# 19_-_USB.net
KiCad netlist of a schematic drawn in Altium Designer
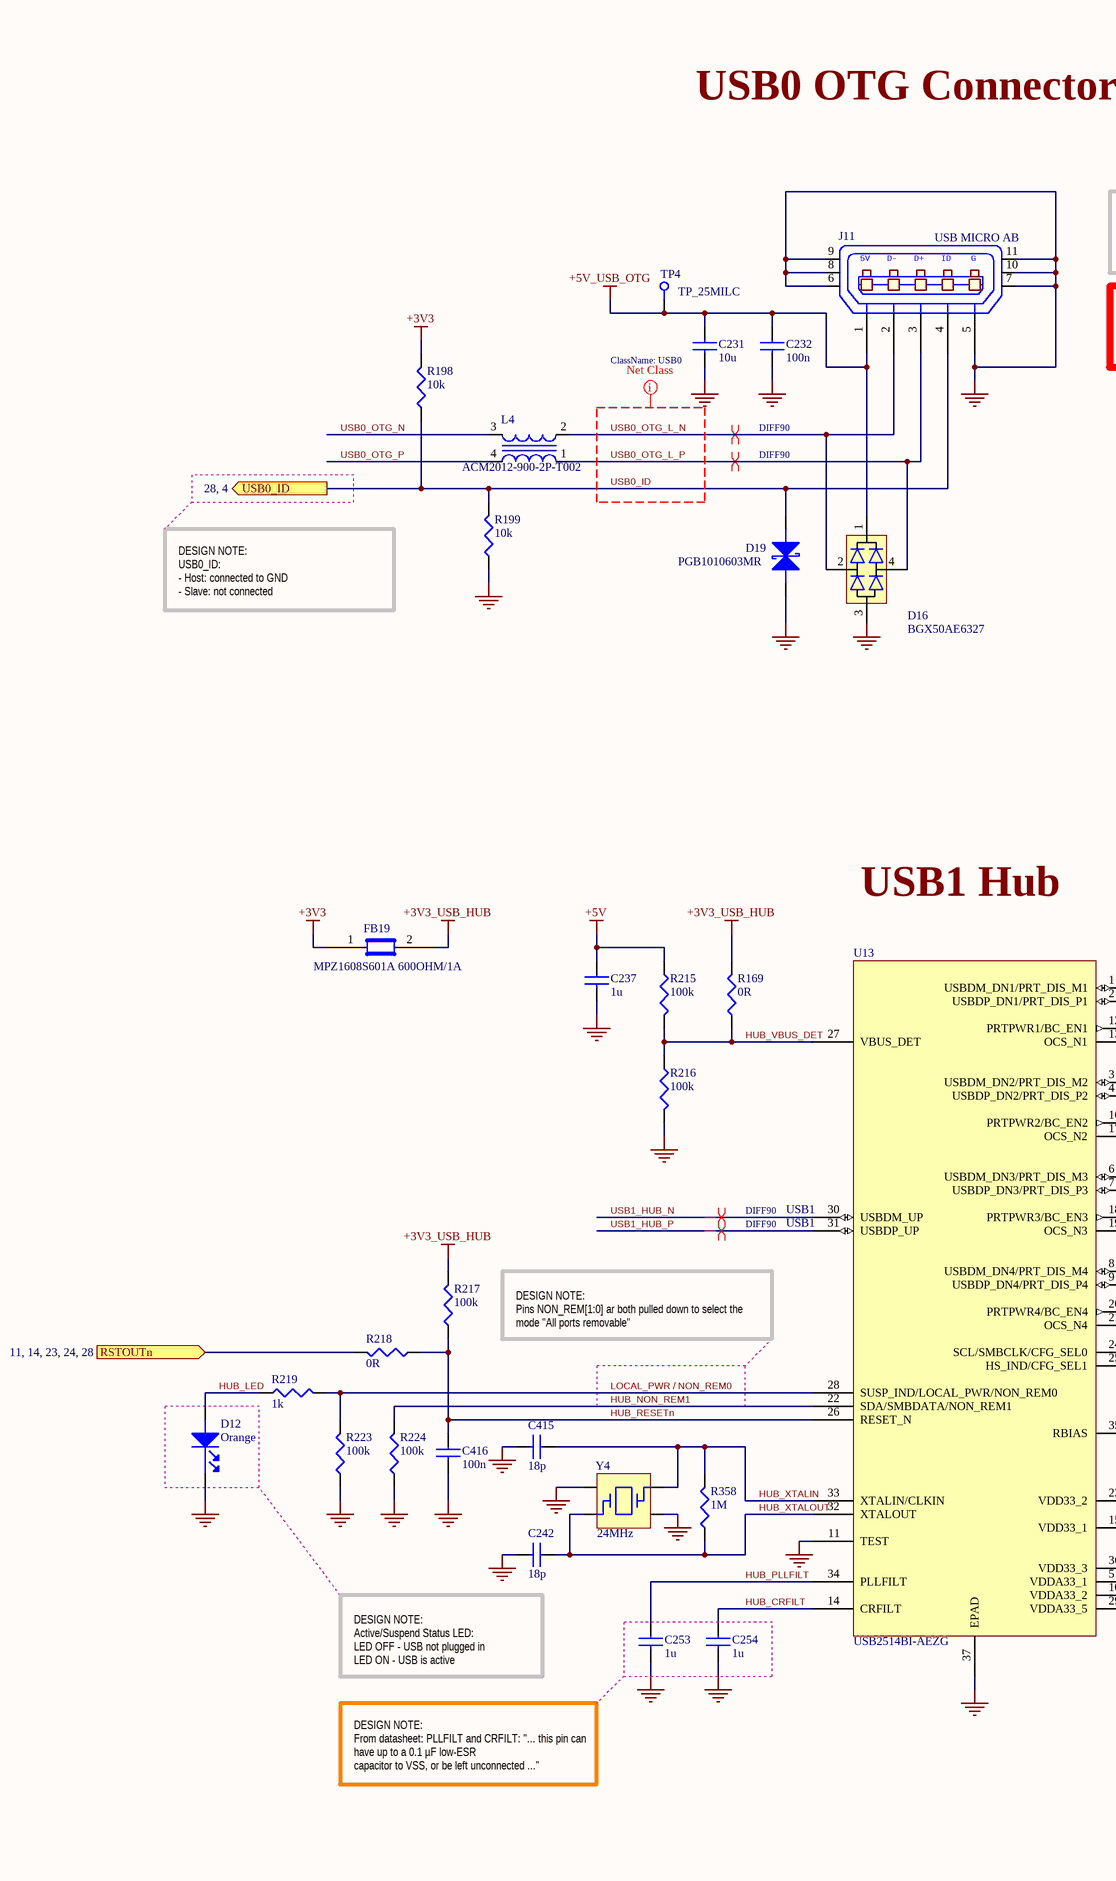
[diagram p0: [19] - USB.SchDoc, left]
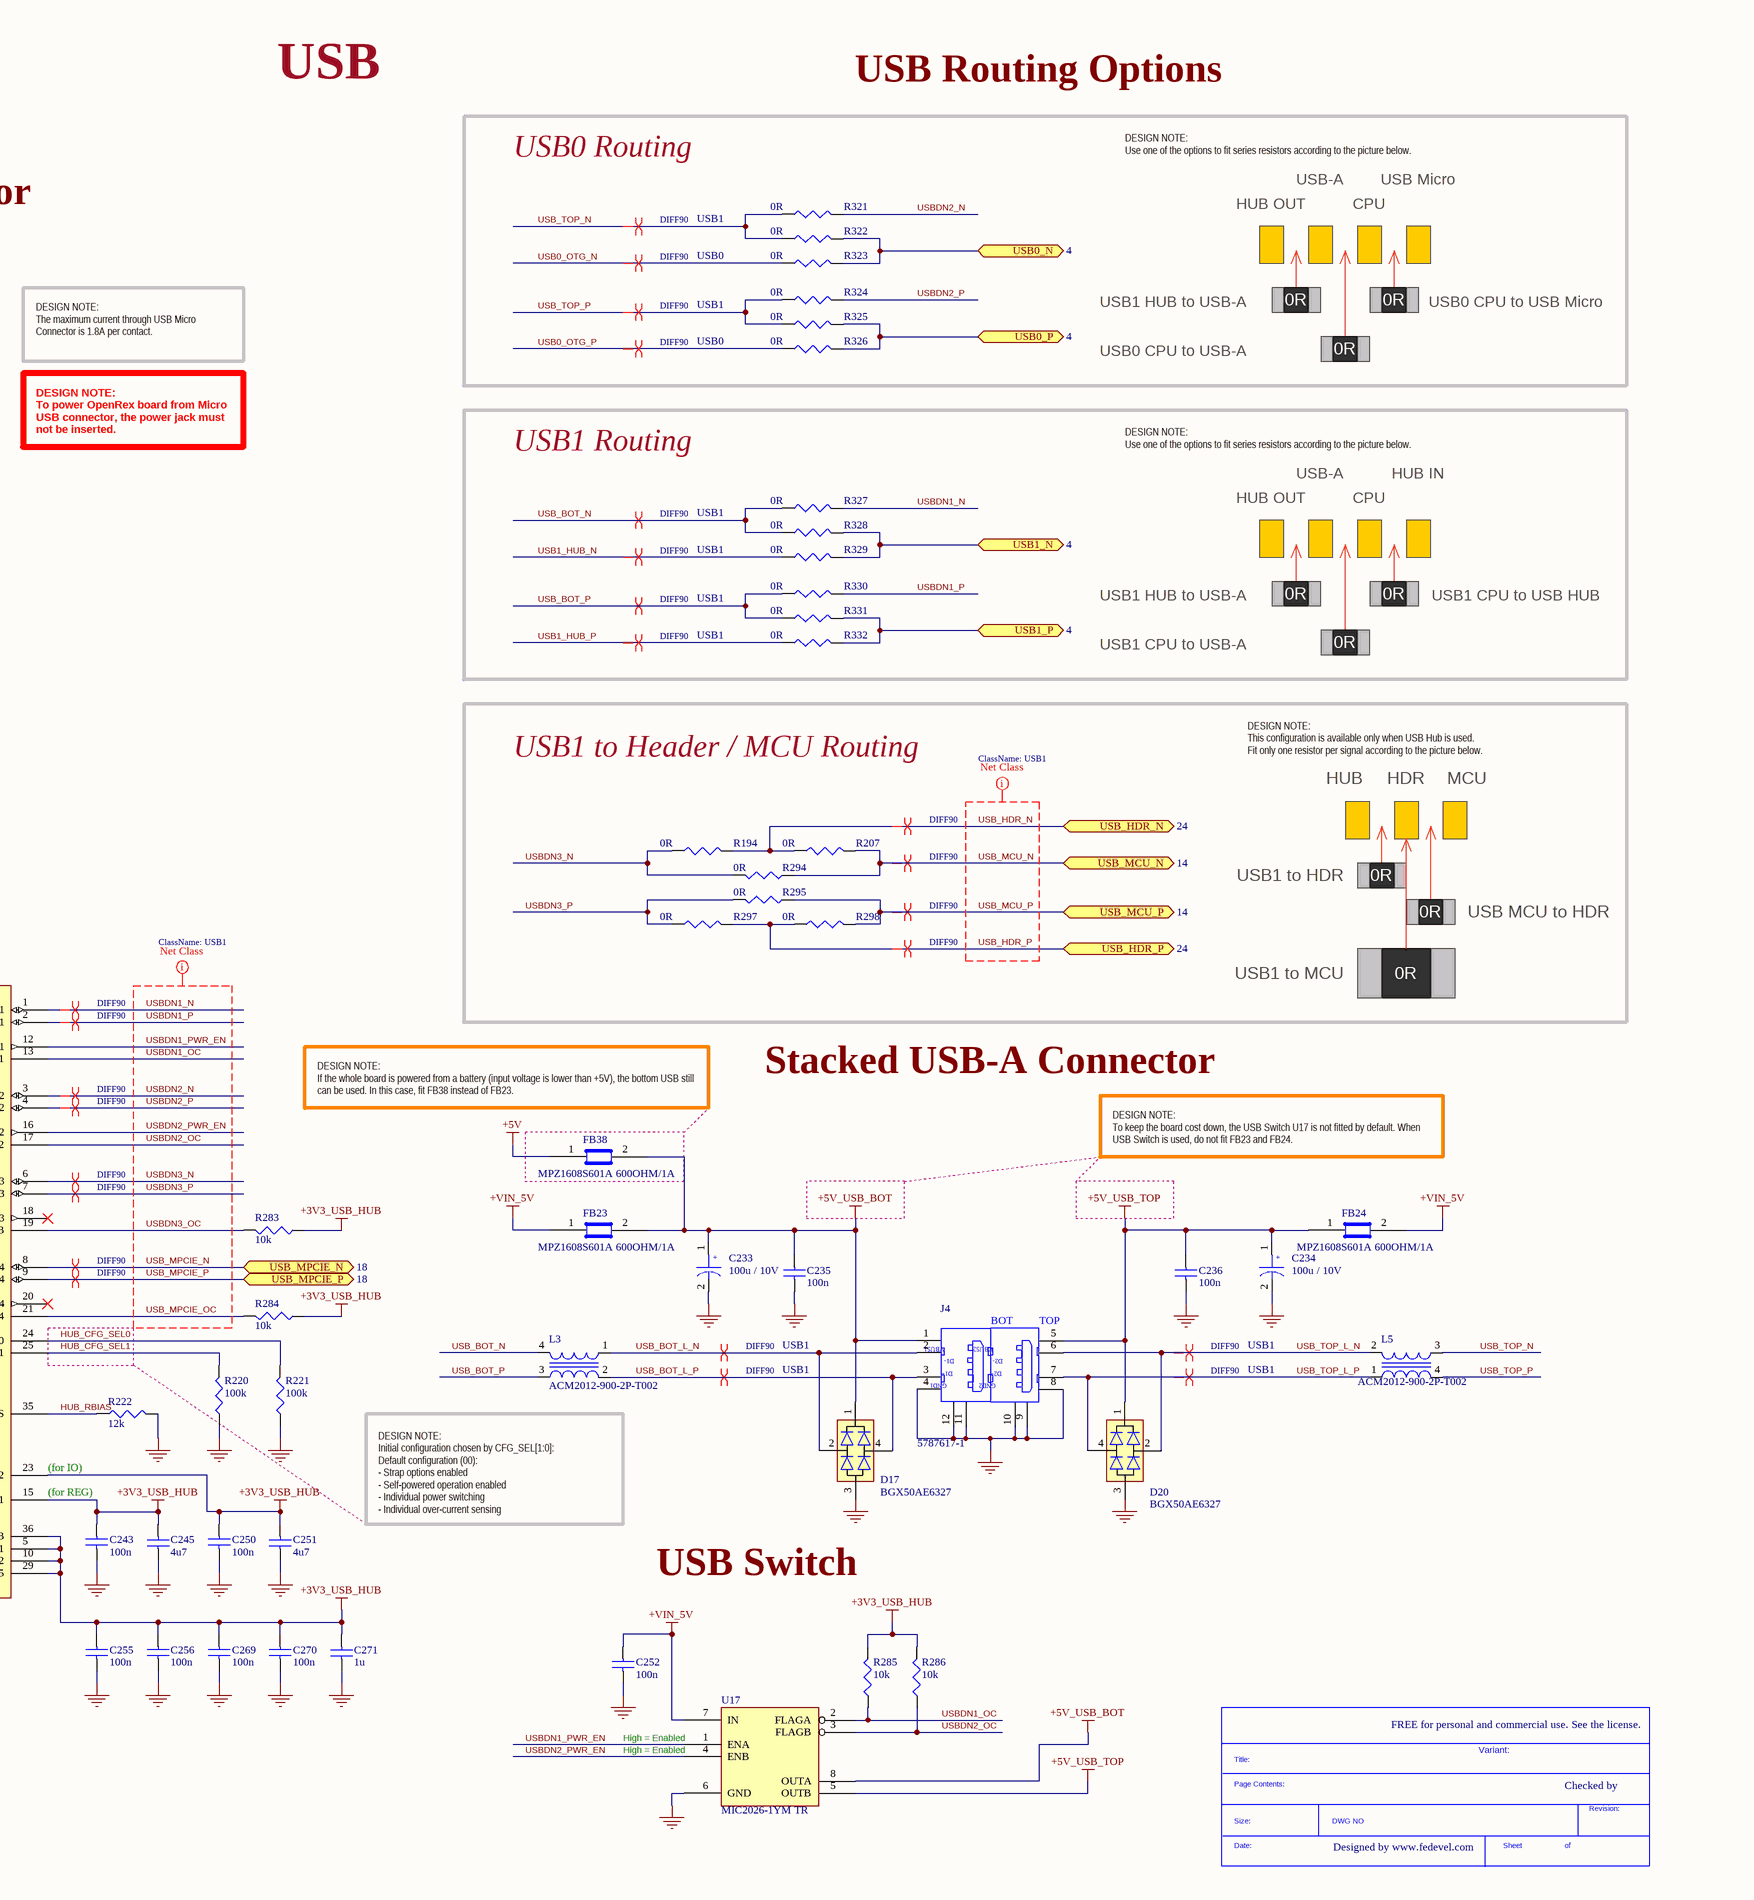
[diagram p1: [19] - USB.SchDoc, right]

(export (version "E")
  (design (tool "Eeschema 10.0.6"))
  (components
    (comp (ref "C231")
      (value "10u")
      (footprint "C0603")
      (description "CAP CER 10UF 6.3V X5R 20% 0603")
      (fields
        (field (name "MANUFACTURER") "TDK Corporation")
        (field (name "MANUFACTURER PART NUMBER") "C1608X5R0J106M")
      )
      (libsource (lib "Integrated_Library_FEDEVEL_APR_2015") (part "C1608X5R0J106M"))
    )
    (comp (ref "C232")
      (value "100n")
      (footprint "C0402")
      (description "CAP CER .10UF 50V X5R 10% 0402")
      (fields
        (field (name "MANUFACTURER") "TDK Corporation")
        (field (name "MANUFACTURER PART NUMBER") "C1005X5R1H104K")
      )
      (libsource (lib "Integrated_Library_FEDEVEL_APR_2015") (part "C1005X5R1H104K"))
    )
    (comp (ref "C233")
      (value "100u / 10V")
      (footprint "C2312")
      (description "CAP TANT 100UF 10V 10% 2312")
      (fields
        (field (name "MANUFACTURER") "AVX Corporation")
        (field (name "MANUFACTURER PART NUMBER") "TPSC107K010R0150")
        (field (name ".CREATOR") "MM")
        (field (name ".CHECKED PCB") "MM")
        (field (name ".CHECKED SCH") "MM")
      )
      (libsource (lib "Integrated_Library_FEDEVEL_APR_2015") (part "TPSC107K010R0150"))
    )
    (comp (ref "C234")
      (value "100u / 10V")
      (footprint "C2312")
      (description "CAP TANT 100UF 10V 10% 2312")
      (fields
        (field (name "MANUFACTURER") "AVX Corporation")
        (field (name "MANUFACTURER PART NUMBER") "TPSC107K010R0150")
        (field (name ".CREATOR") "MM")
        (field (name ".CHECKED PCB") "MM")
        (field (name ".CHECKED SCH") "MM")
      )
      (libsource (lib "Integrated_Library_FEDEVEL_APR_2015") (part "TPSC107K010R0150"))
    )
    (comp (ref "C235")
      (value "100n")
      (footprint "C0402")
      (description "CAP CER .10UF 50V X5R 10% 0402")
      (fields
        (field (name "MANUFACTURER") "TDK Corporation")
        (field (name "MANUFACTURER PART NUMBER") "C1005X5R1H104K")
      )
      (libsource (lib "Integrated_Library_FEDEVEL_APR_2015") (part "C1005X5R1H104K"))
    )
    (comp (ref "C236")
      (value "100n")
      (footprint "C0402")
      (description "CAP CER .10UF 50V X5R 10% 0402")
      (fields
        (field (name "MANUFACTURER") "TDK Corporation")
        (field (name "MANUFACTURER PART NUMBER") "C1005X5R1H104K")
      )
      (libsource (lib "Integrated_Library_FEDEVEL_APR_2015") (part "C1005X5R1H104K"))
    )
    (comp (ref "C237")
      (value "1u")
      (footprint "C0402")
      (description "CAP CER 1.0UF 16V X5R 0402")
      (fields
        (field (name "MANUFACTURER") "TDK Corporation")
        (field (name "MANUFACTURER PART NUMBER") "C1005X5R1C105K")
      )
      (libsource (lib "Integrated_Library_FEDEVEL_APR_2015") (part "C1005X5R1C105K"))
    )
    (comp (ref "C242")
      (value "18p")
      (footprint "C0402")
      (description "CAP CER 18PF 50V C0G 5% 0402")
      (fields
        (field (name "MANUFACTURER") "TDK Corporation")
        (field (name "MANUFACTURER PART NUMBER") "C1005C0G1H180J")
      )
      (libsource (lib "Integrated_Library_FEDEVEL_APR_2015") (part "C1005C0G1H180J"))
    )
    (comp (ref "C243")
      (value "100n")
      (footprint "C0402")
      (description "CAP CER .10UF 50V X5R 10% 0402")
      (fields
        (field (name "MANUFACTURER") "TDK Corporation")
        (field (name "MANUFACTURER PART NUMBER") "C1005X5R1H104K")
      )
      (libsource (lib "Integrated_Library_FEDEVEL_APR_2015") (part "C1005X5R1H104K"))
    )
    (comp (ref "C245")
      (value "4u7")
      (footprint "C0402")
      (description "CAP CER 4.7UF 10V 20% X5R 0402")
      (fields
        (field (name "MANUFACTURER") "TDK Corporation")
        (field (name "MANUFACTURER PART NUMBER") "C1005X5R1A475M")
      )
      (libsource (lib "Integrated_Library_FEDEVEL_APR_2015") (part "C1005X5R1A475M"))
    )
    (comp (ref "C250")
      (value "100n")
      (footprint "C0402")
      (description "CAP CER .10UF 50V X5R 10% 0402")
      (fields
        (field (name "MANUFACTURER") "TDK Corporation")
        (field (name "MANUFACTURER PART NUMBER") "C1005X5R1H104K")
      )
      (libsource (lib "Integrated_Library_FEDEVEL_APR_2015") (part "C1005X5R1H104K"))
    )
    (comp (ref "C251")
      (value "4u7")
      (footprint "C0402")
      (description "CAP CER 4.7UF 10V 20% X5R 0402")
      (fields
        (field (name "MANUFACTURER") "TDK Corporation")
        (field (name "MANUFACTURER PART NUMBER") "C1005X5R1A475M")
      )
      (libsource (lib "Integrated_Library_FEDEVEL_APR_2015") (part "C1005X5R1A475M"))
    )
    (comp (ref "C252")
      (value "100n")
      (footprint "C0402")
      (description "CAP CER .10UF 50V X5R 10% 0402")
      (fields
        (field (name "MANUFACTURER") "TDK Corporation")
        (field (name "MANUFACTURER PART NUMBER") "C1005X5R1H104K")
      )
      (libsource (lib "Integrated_Library_FEDEVEL_APR_2015") (part "C1005X5R1H104K"))
    )
    (comp (ref "C253")
      (value "1u")
      (footprint "C0402")
      (description "CAP CER 1.0UF 16V X5R 0402")
      (fields
        (field (name "MANUFACTURER") "TDK Corporation")
        (field (name "MANUFACTURER PART NUMBER") "C1005X5R1C105K")
      )
      (libsource (lib "Integrated_Library_FEDEVEL_APR_2015") (part "C1005X5R1C105K"))
    )
    (comp (ref "C254")
      (value "1u")
      (footprint "C0402")
      (description "CAP CER 1.0UF 16V X5R 0402")
      (fields
        (field (name "MANUFACTURER") "TDK Corporation")
        (field (name "MANUFACTURER PART NUMBER") "C1005X5R1C105K")
      )
      (libsource (lib "Integrated_Library_FEDEVEL_APR_2015") (part "C1005X5R1C105K"))
    )
    (comp (ref "C255")
      (value "100n")
      (footprint "C0402")
      (description "CAP CER .10UF 50V X5R 10% 0402")
      (fields
        (field (name "MANUFACTURER") "TDK Corporation")
        (field (name "MANUFACTURER PART NUMBER") "C1005X5R1H104K")
      )
      (libsource (lib "Integrated_Library_FEDEVEL_APR_2015") (part "C1005X5R1H104K"))
    )
    (comp (ref "C256")
      (value "100n")
      (footprint "C0402")
      (description "CAP CER .10UF 50V X5R 10% 0402")
      (fields
        (field (name "MANUFACTURER") "TDK Corporation")
        (field (name "MANUFACTURER PART NUMBER") "C1005X5R1H104K")
      )
      (libsource (lib "Integrated_Library_FEDEVEL_APR_2015") (part "C1005X5R1H104K"))
    )
    (comp (ref "C269")
      (value "100n")
      (footprint "C0402")
      (description "CAP CER .10UF 50V X5R 10% 0402")
      (fields
        (field (name "MANUFACTURER") "TDK Corporation")
        (field (name "MANUFACTURER PART NUMBER") "C1005X5R1H104K")
      )
      (libsource (lib "Integrated_Library_FEDEVEL_APR_2015") (part "C1005X5R1H104K"))
    )
    (comp (ref "C270")
      (value "100n")
      (footprint "C0402")
      (description "CAP CER .10UF 50V X5R 10% 0402")
      (fields
        (field (name "MANUFACTURER") "TDK Corporation")
        (field (name "MANUFACTURER PART NUMBER") "C1005X5R1H104K")
      )
      (libsource (lib "Integrated_Library_FEDEVEL_APR_2015") (part "C1005X5R1H104K"))
    )
    (comp (ref "C271")
      (value "1u")
      (footprint "C0402")
      (description "CAP CER 1.0UF 16V X5R 0402")
      (fields
        (field (name "MANUFACTURER") "TDK Corporation")
        (field (name "MANUFACTURER PART NUMBER") "C1005X5R1C105K")
      )
      (libsource (lib "Integrated_Library_FEDEVEL_APR_2015") (part "C1005X5R1C105K"))
    )
    (comp (ref "C415")
      (value "18p")
      (footprint "C0402")
      (description "CAP CER 18PF 50V C0G 5% 0402")
      (fields
        (field (name "MANUFACTURER") "TDK Corporation")
        (field (name "MANUFACTURER PART NUMBER") "C1005C0G1H180J")
      )
      (libsource (lib "Integrated_Library_FEDEVEL_APR_2015") (part "C1005C0G1H180J"))
    )
    (comp (ref "C416")
      (value "100n")
      (footprint "C0402")
      (description "CAP CER .10UF 50V X5R 10% 0402")
      (fields
        (field (name "MANUFACTURER") "TDK Corporation")
        (field (name "MANUFACTURER PART NUMBER") "C1005X5R1H104K")
      )
      (libsource (lib "Integrated_Library_FEDEVEL_APR_2015") (part "C1005X5R1H104K"))
    )
    (comp (ref "D12")
      (value "Orange")
      (footprint "LED_0603")
      (description "LED SMARTLED ORANGE 606NM 0603")
      (fields
        (field (name "MANUFACTURER") "OSRAM Opto Semiconductors Inc")
        (field (name "MANUFACTURER PART NUMBER") "LO L29K-H2K1-24-Z")
      )
      (libsource (lib "Integrated_Library_FEDEVEL_APR_2015") (part "LO L29K-H2K1-24-Z"))
    )
    (comp (ref "D16")
      (value "BGX50AE6327")
      (footprint "SOT143")
      (description "DIODE SWITCHING 50V SOT-143")
      (fields (field (name "MANUFACTURER") "Infineon Technologies"))
      (libsource (lib "Integrated_Library_FEDEVEL_APR_2015") (part "BGX50AE6327"))
    )
    (comp (ref "D17")
      (value "BGX50AE6327")
      (footprint "SOT143")
      (description "DIODE SWITCHING 50V SOT-143")
      (fields (field (name "MANUFACTURER") "Infineon Technologies"))
      (libsource (lib "Integrated_Library_FEDEVEL_APR_2015") (part "BGX50AE6327"))
    )
    (comp (ref "D19")
      (value "PGB1010603MR")
      (footprint "C0603")
      (description "SUPPRESSOR ESD 24VDC 0603 SMD")
      (fields (field (name "MANUFACTURER") "Littelfuse Inc") (field (name ".CREATOR") "MM"))
      (libsource (lib "Integrated_Library_FEDEVEL_APR_2015") (part "PGB1010603MR"))
    )
    (comp (ref "D20")
      (value "BGX50AE6327")
      (footprint "SOT143")
      (description "DIODE SWITCHING 50V SOT-143")
      (fields (field (name "MANUFACTURER") "Infineon Technologies"))
      (libsource (lib "") (part "BGX50AE6327_1"))
    )
    (comp (ref "FB19")
      (value "MPZ1608S601A 600OHM/1A")
      (footprint "C0603")
      (description "FERRITE CHIP BEAD 600 OHM SMD 1A")
      (fields
        (field (name "MANUFACTURER") "TDK Corporation")
        (field (name "MANUFACTURER PART NUMBER") "MPZ1608S601A")
      )
      (libsource (lib "Integrated_Library_FEDEVEL_APR_2015") (part "MPZ1608S601A"))
    )
    (comp (ref "FB23")
      (value "MPZ1608S601A 600OHM/1A")
      (footprint "C0603")
      (description "FERRITE CHIP BEAD 600 OHM SMD 1A")
      (fields
        (field (name "MANUFACTURER") "TDK Corporation")
        (field (name "MANUFACTURER PART NUMBER") "MPZ1608S601A")
      )
      (libsource (lib "Integrated_Library_FEDEVEL_APR_2015") (part "MPZ1608S601A"))
    )
    (comp (ref "FB24")
      (value "MPZ1608S601A 600OHM/1A")
      (footprint "C0603")
      (description "FERRITE CHIP BEAD 600 OHM SMD 1A")
      (fields
        (field (name "MANUFACTURER") "TDK Corporation")
        (field (name "MANUFACTURER PART NUMBER") "MPZ1608S601A")
      )
      (libsource (lib "Integrated_Library_FEDEVEL_APR_2015") (part "MPZ1608S601A"))
    )
    (comp (ref "FB38")
      (value "MPZ1608S601A 600OHM/1A")
      (footprint "C0603")
      (description "FERRITE CHIP BEAD 600 OHM SMD 1A")
      (fields
        (field (name "MANUFACTURER") "TDK Corporation")
        (field (name "MANUFACTURER PART NUMBER") "MPZ1608S601A")
      )
      (libsource (lib "Integrated_Library_FEDEVEL_APR_2015") (part "MPZ1608S601A"))
    )
    (comp (ref "J4")
      (value "5787617-1")
      (footprint "USB-2A")
      (description "CONN RCPT R/A 4OVER4POS GOLD PCB")
      (fields
        (field (name "MANUFACTURER") "TE Connectivity")
        (field (name ".CHECKED SCH") "MM")
        (field (name ".CREATOR") "MM")
      )
      (libsource (lib "Integrated_Library_FEDEVEL_APR_2015") (part "5787617-1_v1.1"))
    )
    (comp (ref "J11")
      (value "USB MICRO AB")
      (footprint "USB_Micro_AB")
      (description "CONN RCPT MICRO USB AB R/A SMD")
      (fields
        (field (name "MANUFACTURER") "Molex Inc")
        (field (name "MANUFACTURER PART NUMBER") "0475890001")
        (field (name ".CREATOR") "MM")
      )
      (libsource (lib "Integrated_Library_FEDEVEL_APR_2015") (part "0475890001"))
    )
    (comp (ref "L3")
      (value "ACM2012-900-2P-T002")
      (footprint "ACM2012")
      (description "CHOKE COMM MODE 90 OHM .4A SMD")
      (fields (field (name "MANUFACTURER") "TDK Corporation") (field (name "TOLERANCE") "±1%"))
      (libsource (lib "Integrated_Library_FEDEVEL_APR_2015") (part "ACM2012-900-2P-T002"))
    )
    (comp (ref "L4")
      (value "ACM2012-900-2P-T002")
      (footprint "ACM2012")
      (description "CHOKE COMM MODE 90 OHM .4A SMD")
      (fields (field (name "MANUFACTURER") "TDK Corporation") (field (name "TOLERANCE") "±1%"))
      (libsource (lib "") (part "ACM2012-900-2P-T002_1"))
    )
    (comp (ref "L5")
      (value "ACM2012-900-2P-T002")
      (footprint "ACM2012")
      (description "CHOKE COMM MODE 90 OHM .4A SMD")
      (fields (field (name "MANUFACTURER") "TDK Corporation") (field (name "TOLERANCE") "±1%"))
      (libsource (lib "Integrated_Library_FEDEVEL_APR_2015") (part "ACM2012-900-2P-T002"))
    )
    (comp (ref "R169")
      (value "0R")
      (footprint "R0402")
      (description "RES 0.0 OHM 1/16W 0402 SMD")
      (fields
        (field (name "MANUFACTURER") "Yageo")
        (field (name "MANUFACTURER PART NUMBER") "RC0402JR-070RL")
      )
      (libsource (lib "Integrated_Library_FEDEVEL_APR_2015") (part "RC0402JR-070RL"))
    )
    (comp (ref "R194")
      (value "0R")
      (footprint "R0402")
      (description "RES 0.0 OHM 1/16W 0402 SMD")
      (fields
        (field (name "MANUFACTURER") "Yageo")
        (field (name "MANUFACTURER PART NUMBER") "RC0402JR-070RL")
      )
      (libsource (lib "Integrated_Library_FEDEVEL_APR_2015") (part "RC0402JR-070RL"))
    )
    (comp (ref "R198")
      (value "10k")
      (footprint "R0402")
      (description "RES 10.0K OHM 1/16W 1% 0402 SMD")
      (fields
        (field (name "MANUFACTURER") "Yageo")
        (field (name "MANUFACTURER PART NUMBER") "RC0402FR-0710KL")
      )
      (libsource (lib "Integrated_Library_FEDEVEL_APR_2015") (part "RC0402FR-0710KL"))
    )
    (comp (ref "R199")
      (value "10k")
      (footprint "R0402")
      (description "RES 10.0K OHM 1/16W 1% 0402 SMD")
      (fields
        (field (name "MANUFACTURER") "Yageo")
        (field (name "MANUFACTURER PART NUMBER") "RC0402FR-0710KL")
      )
      (libsource (lib "Integrated_Library_FEDEVEL_APR_2015") (part "RC0402FR-0710KL"))
    )
    (comp (ref "R207")
      (value "0R")
      (footprint "R0402")
      (description "RES 0.0 OHM 1/16W 0402 SMD")
      (fields
        (field (name "MANUFACTURER") "Yageo")
        (field (name "MANUFACTURER PART NUMBER") "RC0402JR-070RL")
      )
      (libsource (lib "Integrated_Library_FEDEVEL_APR_2015") (part "RC0402JR-070RL"))
    )
    (comp (ref "R215")
      (value "100k")
      (footprint "R0402")
      (description "RES 100K OHM 1/16W 1% 0402 SMD")
      (fields
        (field (name "MANUFACTURER") "Stackpole Electronics Inc")
        (field (name "MANUFACTURER PART NUMBER") "RMCF0402FT100K")
      )
      (libsource (lib "Integrated_Library_FEDEVEL_APR_2015") (part "RMCF0402FT100K"))
    )
    (comp (ref "R216")
      (value "100k")
      (footprint "R0402")
      (description "RES 100K OHM 1/16W 1% 0402 SMD")
      (fields
        (field (name "MANUFACTURER") "Stackpole Electronics Inc")
        (field (name "MANUFACTURER PART NUMBER") "RMCF0402FT100K")
      )
      (libsource (lib "Integrated_Library_FEDEVEL_APR_2015") (part "RMCF0402FT100K"))
    )
    (comp (ref "R217")
      (value "100k")
      (footprint "R0402")
      (description "RES 100K OHM 1/16W 1% 0402 SMD")
      (fields
        (field (name "MANUFACTURER") "Stackpole Electronics Inc")
        (field (name "MANUFACTURER PART NUMBER") "RMCF0402FT100K")
      )
      (libsource (lib "Integrated_Library_FEDEVEL_APR_2015") (part "RMCF0402FT100K"))
    )
    (comp (ref "R218")
      (value "0R")
      (footprint "R0402")
      (description "RES 0.0 OHM 1/16W 0402 SMD")
      (fields
        (field (name "MANUFACTURER") "Yageo")
        (field (name "MANUFACTURER PART NUMBER") "RC0402JR-070RL")
      )
      (libsource (lib "Integrated_Library_FEDEVEL_APR_2015") (part "RC0402JR-070RL"))
    )
    (comp (ref "R219")
      (value "1k")
      (footprint "R0402")
      (description "RES 1.00K OHM 1/16W 1% 0402 SMD")
      (fields
        (field (name "MANUFACTURER") "Yageo")
        (field (name "MANUFACTURER PART NUMBER") "RC0402FR-071KL")
      )
      (libsource (lib "Integrated_Library_FEDEVEL_APR_2015") (part "RC0402FR-071KL"))
    )
    (comp (ref "R220")
      (value "100k")
      (footprint "R0402")
      (description "RES 100K OHM 1/16W 1% 0402 SMD")
      (fields
        (field (name "MANUFACTURER") "Stackpole Electronics Inc")
        (field (name "MANUFACTURER PART NUMBER") "RMCF0402FT100K")
      )
      (libsource (lib "Integrated_Library_FEDEVEL_APR_2015") (part "RMCF0402FT100K"))
    )
    (comp (ref "R221")
      (value "100k")
      (footprint "R0402")
      (description "RES 100K OHM 1/16W 1% 0402 SMD")
      (fields
        (field (name "MANUFACTURER") "Stackpole Electronics Inc")
        (field (name "MANUFACTURER PART NUMBER") "RMCF0402FT100K")
      )
      (libsource (lib "Integrated_Library_FEDEVEL_APR_2015") (part "RMCF0402FT100K"))
    )
    (comp (ref "R222")
      (value "12k")
      (footprint "R0402")
      (description "RES 12.0K OHM 1/16W 1% 0402 SMD")
      (fields
        (field (name "MANUFACTURER") "Yageo")
        (field (name "MANUFACTURER PART NUMBER") "RC0402FR-0712KL")
      )
      (libsource (lib "Integrated_Library_FEDEVEL_APR_2015") (part "RC0402FR-0712KL"))
    )
    (comp (ref "R223")
      (value "100k")
      (footprint "R0402")
      (description "RES 100K OHM 1/16W 1% 0402 SMD")
      (fields
        (field (name "MANUFACTURER") "Stackpole Electronics Inc")
        (field (name "MANUFACTURER PART NUMBER") "RMCF0402FT100K")
      )
      (libsource (lib "Integrated_Library_FEDEVEL_APR_2015") (part "RMCF0402FT100K"))
    )
    (comp (ref "R224")
      (value "100k")
      (footprint "R0402")
      (description "RES 100K OHM 1/16W 1% 0402 SMD")
      (fields
        (field (name "MANUFACTURER") "Stackpole Electronics Inc")
        (field (name "MANUFACTURER PART NUMBER") "RMCF0402FT100K")
      )
      (libsource (lib "Integrated_Library_FEDEVEL_APR_2015") (part "RMCF0402FT100K"))
    )
    (comp (ref "R283")
      (value "10k")
      (footprint "R0402")
      (description "RES 10.0K OHM 1/16W 1% 0402 SMD")
      (fields
        (field (name "MANUFACTURER") "Yageo")
        (field (name "MANUFACTURER PART NUMBER") "RC0402FR-0710KL")
      )
      (libsource (lib "Integrated_Library_FEDEVEL_APR_2015") (part "RC0402FR-0710KL"))
    )
    (comp (ref "R284")
      (value "10k")
      (footprint "R0402")
      (description "RES 10.0K OHM 1/16W 1% 0402 SMD")
      (fields
        (field (name "MANUFACTURER") "Yageo")
        (field (name "MANUFACTURER PART NUMBER") "RC0402FR-0710KL")
      )
      (libsource (lib "Integrated_Library_FEDEVEL_APR_2015") (part "RC0402FR-0710KL"))
    )
    (comp (ref "R285")
      (value "10k")
      (footprint "R0402")
      (description "RES 10.0K OHM 1/16W 1% 0402 SMD")
      (fields
        (field (name "MANUFACTURER") "Yageo")
        (field (name "MANUFACTURER PART NUMBER") "RC0402FR-0710KL")
      )
      (libsource (lib "Integrated_Library_FEDEVEL_APR_2015") (part "RC0402FR-0710KL"))
    )
    (comp (ref "R286")
      (value "10k")
      (footprint "R0402")
      (description "RES 10.0K OHM 1/16W 1% 0402 SMD")
      (fields
        (field (name "MANUFACTURER") "Yageo")
        (field (name "MANUFACTURER PART NUMBER") "RC0402FR-0710KL")
      )
      (libsource (lib "Integrated_Library_FEDEVEL_APR_2015") (part "RC0402FR-0710KL"))
    )
    (comp (ref "R294")
      (value "0R")
      (footprint "R0805_small")
      (description "RES 0.0 OHM 1/8W 0805 SMD")
      (fields
        (field (name "MANUFACTURER") "Yageo")
        (field (name "MANUFACTURER PART NUMBER") "RC0805JR-070RL")
        (field (name ".CHECKED PCB") "MM")
        (field (name ".CHECKED SCH") "MM")
        (field (name ".CREATOR") "MM")
      )
      (libsource (lib "Integrated_Library_FEDEVEL_APR_2015") (part "RC0805JR-070RL_small"))
    )
    (comp (ref "R295")
      (value "0R")
      (footprint "R0805_small")
      (description "RES 0.0 OHM 1/8W 0805 SMD")
      (fields
        (field (name "MANUFACTURER") "Yageo")
        (field (name "MANUFACTURER PART NUMBER") "RC0805JR-070RL")
        (field (name ".CHECKED PCB") "MM")
        (field (name ".CHECKED SCH") "MM")
        (field (name ".CREATOR") "MM")
      )
      (libsource (lib "Integrated_Library_FEDEVEL_APR_2015") (part "RC0805JR-070RL_small"))
    )
    (comp (ref "R297")
      (value "0R")
      (footprint "R0402")
      (description "RES 0.0 OHM 1/16W 0402 SMD")
      (fields
        (field (name "MANUFACTURER") "Yageo")
        (field (name "MANUFACTURER PART NUMBER") "RC0402JR-070RL")
      )
      (libsource (lib "Integrated_Library_FEDEVEL_APR_2015") (part "RC0402JR-070RL"))
    )
    (comp (ref "R298")
      (value "0R")
      (footprint "R0402")
      (description "RES 0.0 OHM 1/16W 0402 SMD")
      (fields
        (field (name "MANUFACTURER") "Yageo")
        (field (name "MANUFACTURER PART NUMBER") "RC0402JR-070RL")
      )
      (libsource (lib "Integrated_Library_FEDEVEL_APR_2015") (part "RC0402JR-070RL"))
    )
    (comp (ref "R321")
      (value "0R")
      (footprint "R0402")
      (description "RES 0.0 OHM 1/16W 0402 SMD")
      (fields
        (field (name "MANUFACTURER") "Yageo")
        (field (name "MANUFACTURER PART NUMBER") "RC0402JR-070RL")
      )
      (libsource (lib "Integrated_Library_FEDEVEL_APR_2015") (part "RC0402JR-070RL"))
    )
    (comp (ref "R322")
      (value "0R")
      (footprint "R0402")
      (description "RES 0.0 OHM 1/16W 0402 SMD")
      (fields
        (field (name "MANUFACTURER") "Yageo")
        (field (name "MANUFACTURER PART NUMBER") "RC0402JR-070RL")
      )
      (libsource (lib "Integrated_Library_FEDEVEL_APR_2015") (part "RC0402JR-070RL"))
    )
    (comp (ref "R323")
      (value "0R")
      (footprint "R0402")
      (description "RES 0.0 OHM 1/16W 0402 SMD")
      (fields
        (field (name "MANUFACTURER") "Yageo")
        (field (name "MANUFACTURER PART NUMBER") "RC0402JR-070RL")
      )
      (libsource (lib "Integrated_Library_FEDEVEL_APR_2015") (part "RC0402JR-070RL"))
    )
    (comp (ref "R324")
      (value "0R")
      (footprint "R0402")
      (description "RES 0.0 OHM 1/16W 0402 SMD")
      (fields
        (field (name "MANUFACTURER") "Yageo")
        (field (name "MANUFACTURER PART NUMBER") "RC0402JR-070RL")
      )
      (libsource (lib "Integrated_Library_FEDEVEL_APR_2015") (part "RC0402JR-070RL"))
    )
    (comp (ref "R325")
      (value "0R")
      (footprint "R0402")
      (description "RES 0.0 OHM 1/16W 0402 SMD")
      (fields
        (field (name "MANUFACTURER") "Yageo")
        (field (name "MANUFACTURER PART NUMBER") "RC0402JR-070RL")
      )
      (libsource (lib "Integrated_Library_FEDEVEL_APR_2015") (part "RC0402JR-070RL"))
    )
    (comp (ref "R326")
      (value "0R")
      (footprint "R0402")
      (description "RES 0.0 OHM 1/16W 0402 SMD")
      (fields
        (field (name "MANUFACTURER") "Yageo")
        (field (name "MANUFACTURER PART NUMBER") "RC0402JR-070RL")
      )
      (libsource (lib "Integrated_Library_FEDEVEL_APR_2015") (part "RC0402JR-070RL"))
    )
    (comp (ref "R327")
      (value "0R")
      (footprint "R0402")
      (description "RES 0.0 OHM 1/16W 0402 SMD")
      (fields
        (field (name "MANUFACTURER") "Yageo")
        (field (name "MANUFACTURER PART NUMBER") "RC0402JR-070RL")
      )
      (libsource (lib "Integrated_Library_FEDEVEL_APR_2015") (part "RC0402JR-070RL"))
    )
    (comp (ref "R328")
      (value "0R")
      (footprint "R0402")
      (description "RES 0.0 OHM 1/16W 0402 SMD")
      (fields
        (field (name "MANUFACTURER") "Yageo")
        (field (name "MANUFACTURER PART NUMBER") "RC0402JR-070RL")
      )
      (libsource (lib "Integrated_Library_FEDEVEL_APR_2015") (part "RC0402JR-070RL"))
    )
    (comp (ref "R329")
      (value "0R")
      (footprint "R0402")
      (description "RES 0.0 OHM 1/16W 0402 SMD")
      (fields
        (field (name "MANUFACTURER") "Yageo")
        (field (name "MANUFACTURER PART NUMBER") "RC0402JR-070RL")
      )
      (libsource (lib "Integrated_Library_FEDEVEL_APR_2015") (part "RC0402JR-070RL"))
    )
    (comp (ref "R330")
      (value "0R")
      (footprint "R0402")
      (description "RES 0.0 OHM 1/16W 0402 SMD")
      (fields
        (field (name "MANUFACTURER") "Yageo")
        (field (name "MANUFACTURER PART NUMBER") "RC0402JR-070RL")
      )
      (libsource (lib "Integrated_Library_FEDEVEL_APR_2015") (part "RC0402JR-070RL"))
    )
    (comp (ref "R331")
      (value "0R")
      (footprint "R0402")
      (description "RES 0.0 OHM 1/16W 0402 SMD")
      (fields
        (field (name "MANUFACTURER") "Yageo")
        (field (name "MANUFACTURER PART NUMBER") "RC0402JR-070RL")
      )
      (libsource (lib "Integrated_Library_FEDEVEL_APR_2015") (part "RC0402JR-070RL"))
    )
    (comp (ref "R332")
      (value "0R")
      (footprint "R0402")
      (description "RES 0.0 OHM 1/16W 0402 SMD")
      (fields
        (field (name "MANUFACTURER") "Yageo")
        (field (name "MANUFACTURER PART NUMBER") "RC0402JR-070RL")
      )
      (libsource (lib "Integrated_Library_FEDEVEL_APR_2015") (part "RC0402JR-070RL"))
    )
    (comp (ref "R358")
      (value "1M")
      (footprint "R0402")
      (description "RES 1.00M OHM 1/16W 1% 0402 SMD")
      (fields
        (field (name "MANUFACTURER") "Yageo")
        (field (name "MANUFACTURER PART NUMBER") "RC0402FR-071ML")
      )
      (libsource (lib "Integrated_Library_FEDEVEL_APR_2015") (part "RC0402FR-071ML"))
    )
    (comp (ref "TP4")
      (value "TP_25MILC")
      (footprint "TP_25C")
      (description "Test Point 25mil")
      (libsource (lib "Integrated_Library_FEDEVEL_APR_2015") (part "TP_25MILC"))
    )
    (comp (ref "U13")
      (value "USB2514BI-AEZG")
      (footprint "QFN36_6mmx6mm")
      (description "USB HUB CONT IND TEMP 36QFNE3")
      (fields (field (name "MANUFACTURER") "Microchip Technology") (field (name ".CREATOR") "MM"))
      (libsource (lib "Integrated_Library_FEDEVEL_APR_2015") (part "USB2514BI-AEZG"))
    )
    (comp (ref "U17")
      (value "MIC2026-1YM TR")
      (footprint "8_SOIC_3.9MM")
      (description "IC SW DISTRIBUTION 2CHAN 8SOIC")
      (fields (field (name "MANUFACTURER") "Micrel Inc"))
      (libsource (lib "Integrated_Library_FEDEVEL_APR_2015") (part "MIC2026-1YM TR"))
    )
    (comp (ref "Y4")
      (value "24MHz")
      (footprint "ABM8")
      (description "CRYSTAL 24MHZ 18PF SMD")
      (fields
        (field (name "MANUFACTURER") "Abracon Corporation")
        (field (name "MANUFACTURER PART NUMBER") "ABM8-24.000MHZ-R60-D-1-W-T")
        (field (name ".CREATOR") "MM")
        (field (name ".CHECKED PCB") "MM")
        (field (name ".CHECKED SCH") "MM")
      )
      (libsource (lib "Integrated_Library_FEDEVEL_APR_2015") (part "ABM8-24.000MHZ-R60-D-1-W-T"))
    )
  )
  (nets
    (net (code "1") (name "+3V3") (class "Default")
      (node (ref "FB19") (pin "1") (pinfunction "1_1") (pintype "passive"))
      (node (ref "R198") (pin "2") (pinfunction "2_2") (pintype "passive"))
    )
    (net (code "2") (name "+3V3_USB_HUB") (class "Default")
      (node (ref "C243") (pin "1") (pinfunction "1_1") (pintype "passive"))
      (node (ref "C245") (pin "2") (pinfunction "2_2") (pintype "passive"))
      (node (ref "C250") (pin "1") (pinfunction "1_1") (pintype "passive"))
      (node (ref "C251") (pin "2") (pinfunction "2_2") (pintype "passive"))
      (node (ref "C255") (pin "1") (pinfunction "1_1") (pintype "passive"))
      (node (ref "C256") (pin "1") (pinfunction "1_1") (pintype "passive"))
      (node (ref "C269") (pin "1") (pinfunction "1_1") (pintype "passive"))
      (node (ref "C270") (pin "1") (pinfunction "1_1") (pintype "passive"))
      (node (ref "C271") (pin "2") (pinfunction "2_2") (pintype "passive"))
      (node (ref "FB19") (pin "2") (pinfunction "2_2") (pintype "passive"))
      (node (ref "R169") (pin "2") (pinfunction "2_2") (pintype "passive"))
      (node (ref "R217") (pin "2") (pinfunction "2_2") (pintype "passive"))
      (node (ref "R283") (pin "1") (pinfunction "1_1") (pintype "passive"))
      (node (ref "R284") (pin "1") (pinfunction "1_1") (pintype "passive"))
      (node (ref "R285") (pin "2") (pinfunction "2_2") (pintype "passive"))
      (node (ref "R286") (pin "2") (pinfunction "2_2") (pintype "passive"))
      (node (ref "U13") (pin "10") (pinfunction "VDDA33_2_10") (pintype "passive"))
      (node (ref "U13") (pin "15") (pinfunction "VDD33_1_15") (pintype "passive"))
      (node (ref "U13") (pin "23") (pinfunction "VDD33_2_23") (pintype "passive"))
      (node (ref "U13") (pin "29") (pinfunction "VDDA33_5_29") (pintype "passive"))
      (node (ref "U13") (pin "36") (pinfunction "VDD33_3_36") (pintype "passive"))
      (node (ref "U13") (pin "5") (pinfunction "VDDA33_1_5") (pintype "passive"))
    )
    (net (code "3") (name "+5V") (class "Default")
      (node (ref "C237") (pin "1") (pinfunction "1_1") (pintype "passive"))
      (node (ref "FB38") (pin "1") (pinfunction "1_1") (pintype "passive"))
      (node (ref "R215") (pin "1") (pinfunction "1_1") (pintype "passive"))
    )
    (net (code "4") (name "+5V_USB_BOT") (class "Default")
      (node (ref "C233") (pin "1") (pinfunction "1_1") (pintype "passive"))
      (node (ref "C235") (pin "1") (pinfunction "1_1") (pintype "passive"))
      (node (ref "D17") (pin "1") (pinfunction "1_1") (pintype "passive"))
      (node (ref "FB23") (pin "2") (pinfunction "2_2") (pintype "passive"))
      (node (ref "FB38") (pin "2") (pinfunction "2_2") (pintype "passive"))
      (node (ref "J4") (pin "1") (pinfunction "VBUS_1") (pintype "passive"))
      (node (ref "U17") (pin "8") (pinfunction "OUTA_8") (pintype "passive"))
    )
    (net (code "5") (name "+5V_USB_OTG") (class "Default")
      (node (ref "C231") (pin "1") (pinfunction "1_1") (pintype "passive"))
      (node (ref "C232") (pin "1") (pinfunction "1_1") (pintype "passive"))
      (node (ref "D16") (pin "1") (pinfunction "1_1") (pintype "passive"))
      (node (ref "J11") (pin "1") (pinfunction "P1_1") (pintype "passive"))
      (node (ref "TP4") (pin "1") (pinfunction "1_1") (pintype "passive"))
    )
    (net (code "6") (name "+5V_USB_TOP") (class "Default")
      (node (ref "C234") (pin "1") (pinfunction "1_1") (pintype "passive"))
      (node (ref "C236") (pin "1") (pinfunction "1_1") (pintype "passive"))
      (node (ref "D20") (pin "1") (pinfunction "1_1") (pintype "passive"))
      (node (ref "FB24") (pin "1") (pinfunction "1_1") (pintype "passive"))
      (node (ref "J4") (pin "5") (pinfunction "VBUS2_5") (pintype "passive"))
      (node (ref "U17") (pin "5") (pinfunction "OUTB_5") (pintype "passive"))
    )
    (net (code "7") (name "+VIN_5V") (class "Default")
      (node (ref "C252") (pin "1") (pinfunction "1_1") (pintype "passive"))
      (node (ref "FB23") (pin "1") (pinfunction "1_1") (pintype "passive"))
      (node (ref "FB24") (pin "2") (pinfunction "2_2") (pintype "passive"))
      (node (ref "U17") (pin "7") (pinfunction "IN_7") (pintype "power_in"))
    )
    (net (code "8") (name "/HUB_CFG_SEL0") (class "Default")
      (node (ref "R221") (pin "2") (pinfunction "2_2") (pintype "passive"))
      (node (ref "U13") (pin "24") (pinfunction "SCL/SMBCLK/CFG_SEL0_24") (pintype "passive"))
    )
    (net (code "9") (name "/HUB_CFG_SEL1") (class "Default")
      (node (ref "R220") (pin "2") (pinfunction "2_2") (pintype "passive"))
      (node (ref "U13") (pin "25") (pinfunction "HS_IND/CFG_SEL1_25") (pintype "passive"))
    )
    (net (code "10") (name "/HUB_CRFILT") (class "Default")
      (node (ref "C254") (pin "1") (pinfunction "1_1") (pintype "passive"))
      (node (ref "U13") (pin "14") (pinfunction "CRFILT_14") (pintype "passive"))
    )
    (net (code "11") (name "/HUB_LED") (class "Default")
      (node (ref "D12") (pin "2") (pinfunction "ANODE_2") (pintype "passive"))
      (node (ref "R219") (pin "1") (pinfunction "1_1") (pintype "passive"))
    )
    (net (code "12") (name "/HUB_NON_REM1") (class "Default")
      (node (ref "R224") (pin "2") (pinfunction "2_2") (pintype "passive"))
      (node (ref "U13") (pin "22") (pinfunction "SDA/SMBDATA/NON_REM1_22") (pintype "passive"))
    )
    (net (code "13") (name "/HUB_PLLFILT") (class "Default")
      (node (ref "C253") (pin "1") (pinfunction "1_1") (pintype "passive"))
      (node (ref "U13") (pin "34") (pinfunction "PLLFILT_34") (pintype "passive"))
    )
    (net (code "14") (name "/HUB_RBIAS") (class "Default")
      (node (ref "R222") (pin "1") (pinfunction "1_1") (pintype "passive"))
      (node (ref "U13") (pin "35") (pinfunction "RBIAS_35") (pintype "passive"))
    )
    (net (code "15") (name "/HUB_RESETn") (class "Default")
      (node (ref "C416") (pin "1") (pinfunction "1_1") (pintype "passive"))
      (node (ref "R217") (pin "1") (pinfunction "1_1") (pintype "passive"))
      (node (ref "R218") (pin "1") (pinfunction "1_1") (pintype "passive"))
      (node (ref "U13") (pin "26") (pinfunction "RESET_N_26") (pintype "passive"))
    )
    (net (code "16") (name "/HUB_VBUS_DET") (class "Default")
      (node (ref "R169") (pin "1") (pinfunction "1_1") (pintype "passive"))
      (node (ref "R215") (pin "2") (pinfunction "2_2") (pintype "passive"))
      (node (ref "R216") (pin "1") (pinfunction "1_1") (pintype "passive"))
      (node (ref "U13") (pin "27") (pinfunction "VBUS_DET_27") (pintype "passive"))
    )
    (net (code "17") (name "/HUB_XTALIN") (class "Default")
      (node (ref "C415") (pin "1") (pinfunction "1_1") (pintype "passive"))
      (node (ref "R358") (pin "2") (pinfunction "2_2") (pintype "passive"))
      (node (ref "U13") (pin "33") (pinfunction "XTALIN/CLKIN_33") (pintype "passive"))
      (node (ref "Y4") (pin "3") (pinfunction "3_3") (pintype "passive"))
    )
    (net (code "18") (name "/HUB_XTALOUT") (class "Default")
      (node (ref "C242") (pin "1") (pinfunction "1_1") (pintype "passive"))
      (node (ref "R358") (pin "1") (pinfunction "1_1") (pintype "passive"))
      (node (ref "U13") (pin "32") (pinfunction "XTALOUT_32") (pintype "passive"))
      (node (ref "Y4") (pin "1") (pinfunction "1_1") (pintype "passive"))
    )
    (net (code "19") (name "/LOCAL_PWR {slash} NON_REM0") (class "Default")
      (node (ref "R219") (pin "2") (pinfunction "2_2") (pintype "passive"))
      (node (ref "R223") (pin "2") (pinfunction "2_2") (pintype "passive"))
      (node (ref "U13") (pin "28") (pinfunction "SUSP_IND/LOCAL_PWR/NON_REM0_28") (pintype "passive"))
    )
    (net (code "20") (name "/RSTOUTn") (class "Default")
      (node (ref "R218") (pin "2") (pinfunction "2_2") (pintype "passive"))
    )
    (net (code "21") (name "/USB0_ID") (class "Default")
      (node (ref "D19") (pin "1") (pinfunction "1_1") (pintype "passive"))
      (node (ref "J11") (pin "4") (pinfunction "P4_4") (pintype "passive"))
      (node (ref "R198") (pin "1") (pinfunction "1_1") (pintype "passive"))
      (node (ref "R199") (pin "2") (pinfunction "2_2") (pintype "passive"))
    )
    (net (code "22") (name "/USB0_N") (class "Default")
      (node (ref "R322") (pin "2") (pinfunction "2_2") (pintype "passive"))
      (node (ref "R323") (pin "2") (pinfunction "2_2") (pintype "passive"))
    )
    (net (code "23") (name "/USB0_OTG_L_N") (class "Default")
      (node (ref "D16") (pin "2") (pinfunction "2_2") (pintype "passive"))
      (node (ref "J11") (pin "2") (pinfunction "P2_2") (pintype "passive"))
      (node (ref "L4") (pin "2") (pinfunction "2_2") (pintype "passive"))
    )
    (net (code "24") (name "/USB0_OTG_L_P") (class "Default")
      (node (ref "D16") (pin "4") (pinfunction "4_4") (pintype "passive"))
      (node (ref "J11") (pin "3") (pinfunction "P3_3") (pintype "passive"))
      (node (ref "L4") (pin "1") (pinfunction "1_1") (pintype "passive"))
    )
    (net (code "25") (name "/USB0_OTG_N") (class "Default")
      (node (ref "L4") (pin "3") (pinfunction "3_3") (pintype "passive"))
      (node (ref "R323") (pin "1") (pinfunction "1_1") (pintype "passive"))
    )
    (net (code "26") (name "/USB0_OTG_P") (class "Default")
      (node (ref "L4") (pin "4") (pinfunction "4_4") (pintype "passive"))
      (node (ref "R326") (pin "1") (pinfunction "1_1") (pintype "passive"))
    )
    (net (code "27") (name "/USB0_P") (class "Default")
      (node (ref "R325") (pin "2") (pinfunction "2_2") (pintype "passive"))
      (node (ref "R326") (pin "2") (pinfunction "2_2") (pintype "passive"))
    )
    (net (code "28") (name "/USB1_HUB_N") (class "Default")
      (node (ref "R329") (pin "1") (pinfunction "1_1") (pintype "passive"))
      (node (ref "U13") (pin "30") (pinfunction "USBDM_UP_30") (pintype "bidirectional"))
    )
    (net (code "29") (name "/USB1_HUB_P") (class "Default")
      (node (ref "R332") (pin "1") (pinfunction "1_1") (pintype "passive"))
      (node (ref "U13") (pin "31") (pinfunction "USBDP_UP_31") (pintype "bidirectional"))
    )
    (net (code "30") (name "/USB1_N") (class "Default")
      (node (ref "R328") (pin "2") (pinfunction "2_2") (pintype "passive"))
      (node (ref "R329") (pin "2") (pinfunction "2_2") (pintype "passive"))
    )
    (net (code "31") (name "/USB1_P") (class "Default")
      (node (ref "R331") (pin "2") (pinfunction "2_2") (pintype "passive"))
      (node (ref "R332") (pin "2") (pinfunction "2_2") (pintype "passive"))
    )
    (net (code "32") (name "/USBDN1_N") (class "Default")
      (node (ref "R327") (pin "2") (pinfunction "2_2") (pintype "passive"))
      (node (ref "U13") (pin "1") (pinfunction "USBDM_DN1/PRT_DIS_M1_1") (pintype "bidirectional"))
    )
    (net (code "33") (name "/USBDN1_OC") (class "Default")
      (node (ref "R285") (pin "1") (pinfunction "1_1") (pintype "passive"))
      (node (ref "U13") (pin "13") (pinfunction "OCS_N1_13") (pintype "passive"))
      (node (ref "U17") (pin "2") (pinfunction "FLAGA_2") (pintype "passive"))
    )
    (net (code "34") (name "/USBDN1_P") (class "Default")
      (node (ref "R330") (pin "2") (pinfunction "2_2") (pintype "passive"))
      (node (ref "U13") (pin "2") (pinfunction "USBDP_DN1/PRT_DIS_P1_2") (pintype "bidirectional"))
    )
    (net (code "35") (name "/USBDN1_PWR_EN") (class "Default")
      (node (ref "U13") (pin "12") (pinfunction "PRTPWR1/BC_EN1_12") (pintype "output"))
      (node (ref "U17") (pin "1") (pinfunction "ENA_1") (pintype "passive"))
    )
    (net (code "36") (name "/USBDN2_N") (class "Default")
      (node (ref "R321") (pin "2") (pinfunction "2_2") (pintype "passive"))
      (node (ref "U13") (pin "3") (pinfunction "USBDM_DN2/PRT_DIS_M2_3") (pintype "bidirectional"))
    )
    (net (code "37") (name "/USBDN2_OC") (class "Default")
      (node (ref "R286") (pin "1") (pinfunction "1_1") (pintype "passive"))
      (node (ref "U13") (pin "17") (pinfunction "OCS_N2_17") (pintype "passive"))
      (node (ref "U17") (pin "3") (pinfunction "FLAGB_3") (pintype "passive"))
    )
    (net (code "38") (name "/USBDN2_P") (class "Default")
      (node (ref "R324") (pin "2") (pinfunction "2_2") (pintype "passive"))
      (node (ref "U13") (pin "4") (pinfunction "USBDP_DN2/PRT_DIS_P2_4") (pintype "bidirectional"))
    )
    (net (code "39") (name "/USBDN2_PWR_EN") (class "Default")
      (node (ref "U13") (pin "16") (pinfunction "PRTPWR2/BC_EN2_16") (pintype "output"))
      (node (ref "U17") (pin "4") (pinfunction "ENB_4") (pintype "passive"))
    )
    (net (code "40") (name "/USBDN3_N") (class "Default")
      (node (ref "R194") (pin "1") (pinfunction "1_1") (pintype "passive"))
      (node (ref "R294") (pin "1") (pinfunction "1_1") (pintype "passive"))
      (node (ref "U13") (pin "6") (pinfunction "USBDM_DN3/PRT_DIS_M3_6") (pintype "bidirectional"))
    )
    (net (code "41") (name "/USBDN3_OC") (class "Default")
      (node (ref "R283") (pin "2") (pinfunction "2_2") (pintype "passive"))
      (node (ref "U13") (pin "19") (pinfunction "OCS_N3_19") (pintype "passive"))
    )
    (net (code "42") (name "/USBDN3_P") (class "Default")
      (node (ref "R295") (pin "2") (pinfunction "2_2") (pintype "passive"))
      (node (ref "R297") (pin "1") (pinfunction "1_1") (pintype "passive"))
      (node (ref "U13") (pin "7") (pinfunction "USBDP_DN3/PRT_DIS_P3_7") (pintype "bidirectional"))
    )
    (net (code "43") (name "/USB_BOT_L_N") (class "Default")
      (node (ref "D17") (pin "2") (pinfunction "2_2") (pintype "passive"))
      (node (ref "J4") (pin "2") (pinfunction "D-_2") (pintype "passive"))
      (node (ref "L3") (pin "1") (pinfunction "1_1") (pintype "passive"))
    )
    (net (code "44") (name "/USB_BOT_L_P") (class "Default")
      (node (ref "D17") (pin "4") (pinfunction "4_4") (pintype "passive"))
      (node (ref "J4") (pin "3") (pinfunction "D+_3") (pintype "passive"))
      (node (ref "L3") (pin "2") (pinfunction "2_2") (pintype "passive"))
    )
    (net (code "45") (name "/USB_BOT_N") (class "Default")
      (node (ref "L3") (pin "4") (pinfunction "4_4") (pintype "passive"))
      (node (ref "R327") (pin "1") (pinfunction "1_1") (pintype "passive"))
      (node (ref "R328") (pin "1") (pinfunction "1_1") (pintype "passive"))
    )
    (net (code "46") (name "/USB_BOT_P") (class "Default")
      (node (ref "L3") (pin "3") (pinfunction "3_3") (pintype "passive"))
      (node (ref "R330") (pin "1") (pinfunction "1_1") (pintype "passive"))
      (node (ref "R331") (pin "1") (pinfunction "1_1") (pintype "passive"))
    )
    (net (code "47") (name "/USB_HDR_N") (class "Default")
      (node (ref "R194") (pin "2") (pinfunction "2_2") (pintype "passive"))
      (node (ref "R207") (pin "1") (pinfunction "1_1") (pintype "passive"))
    )
    (net (code "48") (name "/USB_HDR_P") (class "Default")
      (node (ref "R297") (pin "2") (pinfunction "2_2") (pintype "passive"))
      (node (ref "R298") (pin "1") (pinfunction "1_1") (pintype "passive"))
    )
    (net (code "49") (name "/USB_MCU_N") (class "Default")
      (node (ref "R207") (pin "2") (pinfunction "2_2") (pintype "passive"))
      (node (ref "R294") (pin "2") (pinfunction "2_2") (pintype "passive"))
    )
    (net (code "50") (name "/USB_MCU_P") (class "Default")
      (node (ref "R295") (pin "1") (pinfunction "1_1") (pintype "passive"))
      (node (ref "R298") (pin "2") (pinfunction "2_2") (pintype "passive"))
    )
    (net (code "51") (name "/USB_MPCIE_N") (class "Default")
      (node (ref "U13") (pin "8") (pinfunction "USBDM_DN4/PRT_DIS_M4_8") (pintype "bidirectional"))
    )
    (net (code "52") (name "/USB_MPCIE_OC") (class "Default")
      (node (ref "R284") (pin "2") (pinfunction "2_2") (pintype "passive"))
      (node (ref "U13") (pin "21") (pinfunction "OCS_N4_21") (pintype "passive"))
    )
    (net (code "53") (name "/USB_MPCIE_P") (class "Default")
      (node (ref "U13") (pin "9") (pinfunction "USBDP_DN4/PRT_DIS_P4_9") (pintype "bidirectional"))
    )
    (net (code "54") (name "/USB_TOP_L_N") (class "Default")
      (node (ref "D20") (pin "2") (pinfunction "2_2") (pintype "passive"))
      (node (ref "J4") (pin "6") (pinfunction "D2-_6") (pintype "passive"))
      (node (ref "L5") (pin "2") (pinfunction "2_2") (pintype "passive"))
    )
    (net (code "55") (name "/USB_TOP_L_P") (class "Default")
      (node (ref "D20") (pin "4") (pinfunction "4_4") (pintype "passive"))
      (node (ref "J4") (pin "7") (pinfunction "D2+_7") (pintype "passive"))
      (node (ref "L5") (pin "1") (pinfunction "1_1") (pintype "passive"))
    )
    (net (code "56") (name "/USB_TOP_N") (class "Default")
      (node (ref "L5") (pin "3") (pinfunction "3_3") (pintype "passive"))
      (node (ref "R321") (pin "1") (pinfunction "1_1") (pintype "passive"))
      (node (ref "R322") (pin "1") (pinfunction "1_1") (pintype "passive"))
    )
    (net (code "57") (name "/USB_TOP_P") (class "Default")
      (node (ref "L5") (pin "4") (pinfunction "4_4") (pintype "passive"))
      (node (ref "R324") (pin "1") (pinfunction "1_1") (pintype "passive"))
      (node (ref "R325") (pin "1") (pinfunction "1_1") (pintype "passive"))
    )
    (net (code "58") (name "GND") (class "Default")
      (node (ref "C231") (pin "2") (pinfunction "2_2") (pintype "passive"))
      (node (ref "C232") (pin "2") (pinfunction "2_2") (pintype "passive"))
      (node (ref "C233") (pin "2") (pinfunction "2_2") (pintype "passive"))
      (node (ref "C234") (pin "2") (pinfunction "2_2") (pintype "passive"))
      (node (ref "C235") (pin "2") (pinfunction "2_2") (pintype "passive"))
      (node (ref "C236") (pin "2") (pinfunction "2_2") (pintype "passive"))
      (node (ref "C237") (pin "2") (pinfunction "2_2") (pintype "passive"))
      (node (ref "C242") (pin "2") (pinfunction "2_2") (pintype "passive"))
      (node (ref "C243") (pin "2") (pinfunction "2_2") (pintype "passive"))
      (node (ref "C245") (pin "1") (pinfunction "1_1") (pintype "passive"))
      (node (ref "C250") (pin "2") (pinfunction "2_2") (pintype "passive"))
      (node (ref "C251") (pin "1") (pinfunction "1_1") (pintype "passive"))
      (node (ref "C252") (pin "2") (pinfunction "2_2") (pintype "passive"))
      (node (ref "C253") (pin "2") (pinfunction "2_2") (pintype "passive"))
      (node (ref "C254") (pin "2") (pinfunction "2_2") (pintype "passive"))
      (node (ref "C255") (pin "2") (pinfunction "2_2") (pintype "passive"))
      (node (ref "C256") (pin "2") (pinfunction "2_2") (pintype "passive"))
      (node (ref "C269") (pin "2") (pinfunction "2_2") (pintype "passive"))
      (node (ref "C270") (pin "2") (pinfunction "2_2") (pintype "passive"))
      (node (ref "C271") (pin "1") (pinfunction "1_1") (pintype "passive"))
      (node (ref "C415") (pin "2") (pinfunction "2_2") (pintype "passive"))
      (node (ref "C416") (pin "2") (pinfunction "2_2") (pintype "passive"))
      (node (ref "D12") (pin "1") (pinfunction "cathode_1") (pintype "passive"))
      (node (ref "D16") (pin "3") (pinfunction "3_3") (pintype "passive"))
      (node (ref "D17") (pin "3") (pinfunction "3_3") (pintype "passive"))
      (node (ref "D19") (pin "2") (pinfunction "2_2") (pintype "passive"))
      (node (ref "D20") (pin "3") (pinfunction "3_3") (pintype "passive"))
      (node (ref "J11") (pin "10") (pinfunction "10_10") (pintype "passive"))
      (node (ref "J11") (pin "11") (pinfunction "11_11") (pintype "passive"))
      (node (ref "J11") (pin "5") (pinfunction "P5_5") (pintype "passive"))
      (node (ref "J11") (pin "6") (pinfunction "6_6") (pintype "passive"))
      (node (ref "J11") (pin "7") (pinfunction "7_7") (pintype "passive"))
      (node (ref "J11") (pin "8") (pinfunction "8_8") (pintype "passive"))
      (node (ref "J11") (pin "9") (pinfunction "9_9") (pintype "passive"))
      (node (ref "J4") (pin "10") (pinfunction "SHIELD_10") (pintype "passive"))
      (node (ref "J4") (pin "11") (pinfunction "SHIELD_11") (pintype "passive"))
      (node (ref "J4") (pin "12") (pinfunction "SHIELD_12") (pintype "passive"))
      (node (ref "J4") (pin "4") (pinfunction "GND_4") (pintype "passive"))
      (node (ref "J4") (pin "8") (pinfunction "GND_8") (pintype "passive"))
      (node (ref "J4") (pin "9") (pinfunction "SHIELD_9") (pintype "passive"))
      (node (ref "R199") (pin "1") (pinfunction "1_1") (pintype "passive"))
      (node (ref "R216") (pin "2") (pinfunction "2_2") (pintype "passive"))
      (node (ref "R220") (pin "1") (pinfunction "1_1") (pintype "passive"))
      (node (ref "R221") (pin "1") (pinfunction "1_1") (pintype "passive"))
      (node (ref "R222") (pin "2") (pinfunction "2_2") (pintype "passive"))
      (node (ref "R223") (pin "1") (pinfunction "1_1") (pintype "passive"))
      (node (ref "R224") (pin "1") (pinfunction "1_1") (pintype "passive"))
      (node (ref "U13") (pin "11") (pinfunction "TEST_11") (pintype "passive"))
      (node (ref "U13") (pin "37") (pinfunction "EPAD_37") (pintype "passive"))
      (node (ref "U17") (pin "6") (pinfunction "GND_6") (pintype "power_in"))
      (node (ref "Y4") (pin "2") (pinfunction "2_2") (pintype "passive"))
      (node (ref "Y4") (pin "4") (pinfunction "4_4") (pintype "passive"))
    )
    (net (code "59") (name "unconnected-(U13-PRTPWR3{slash}BC_EN3-Pad18)") (class "Default")
      (node (ref "U13") (pin "18") (pinfunction "PRTPWR3/BC_EN3_18") (pintype "output+no_connect"))
    )
    (net (code "60") (name "unconnected-(U13-PRTPWR4{slash}BC_EN4-Pad20)") (class "Default")
      (node (ref "U13") (pin "20") (pinfunction "PRTPWR4/BC_EN4_20") (pintype "output+no_connect"))
    )
  )
)
